# PLO2_v1.net
KiCad netlist of a schematic drawn in EAGLE
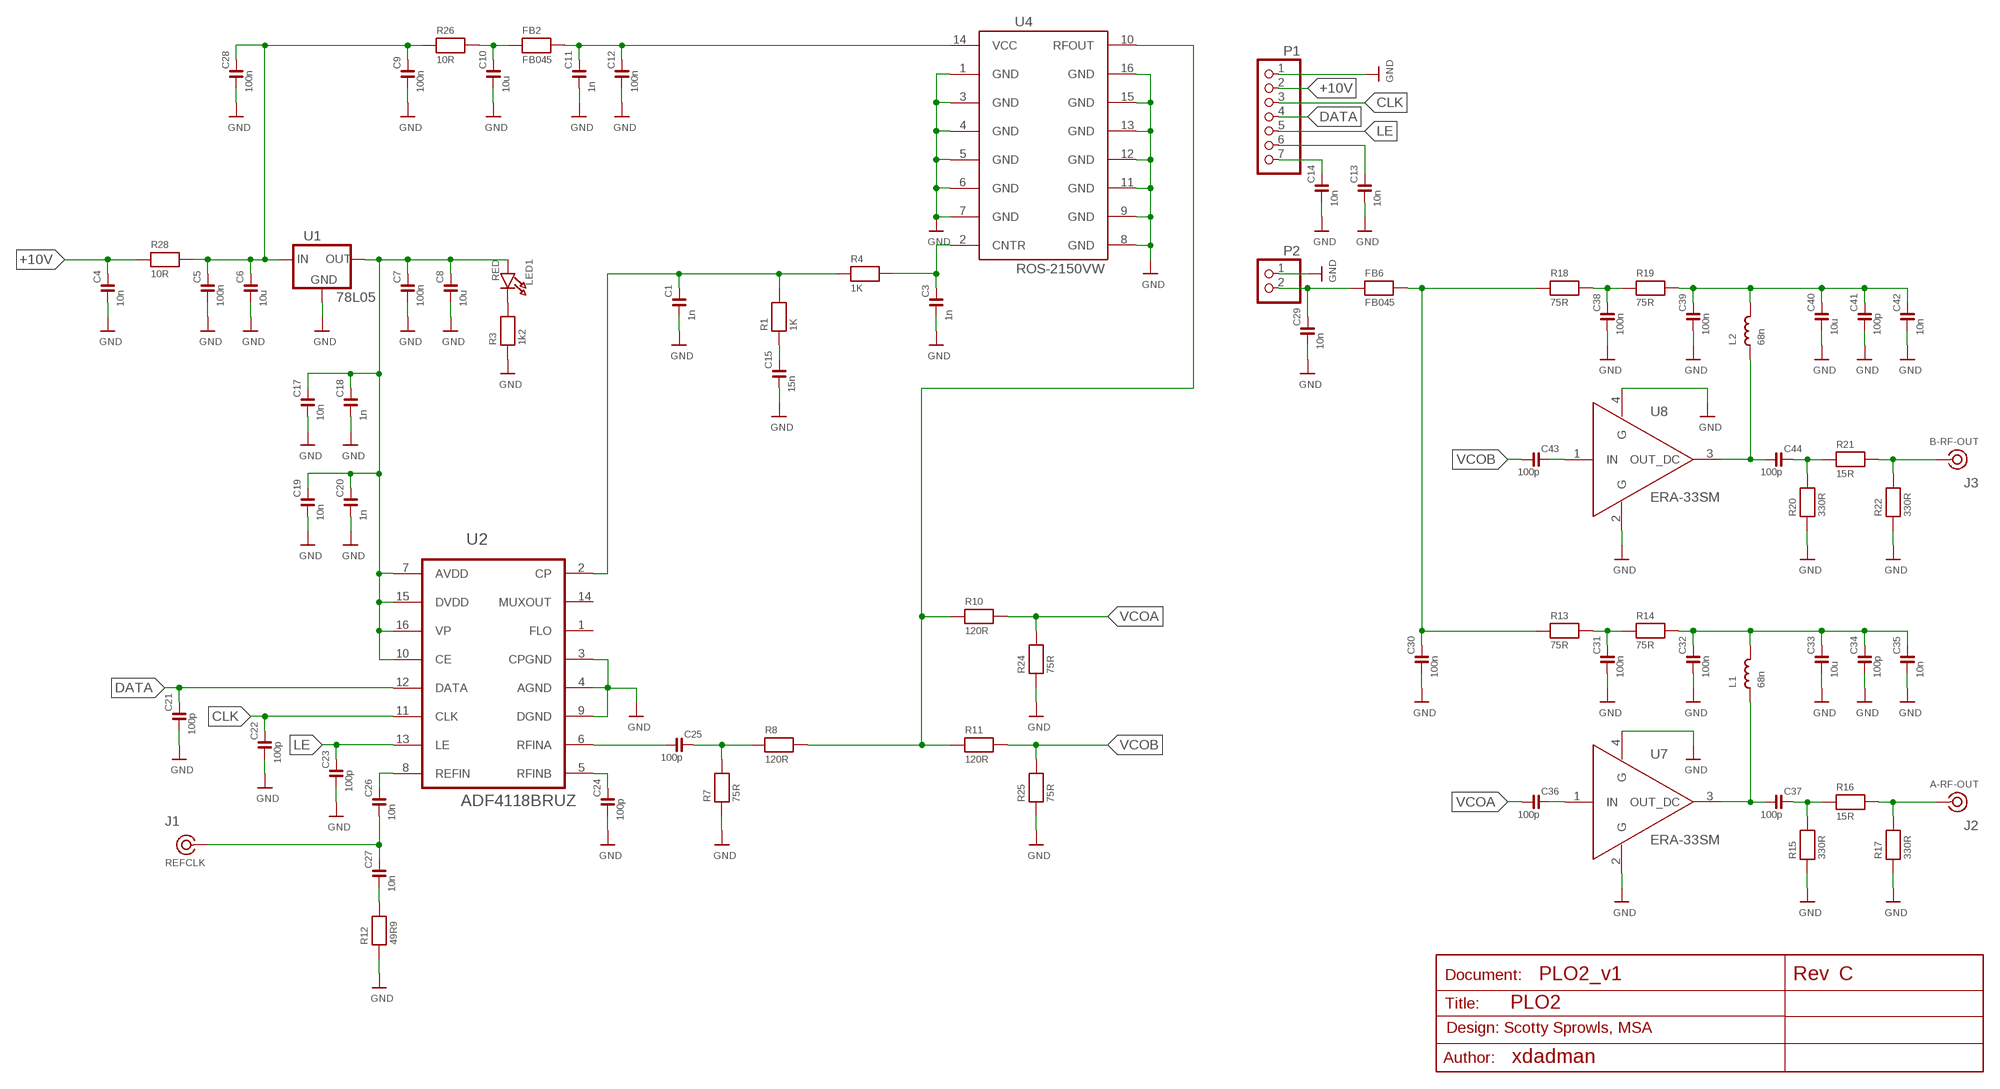
[diagram p0: schematic, sheet 1]

(export (version "E")
  (design (tool "Eeschema 10.0.6"))
  (components
    (comp (ref "C1")
      (value "1n")
      (footprint "eagle-import:C0805")
      (libsource (lib "eagle-import") (part "C08051N"))
    )
    (comp (ref "C3")
      (value "1n")
      (footprint "eagle-import:C0805")
      (libsource (lib "eagle-import") (part "C08051N"))
    )
    (comp (ref "C4")
      (value "10n")
      (footprint "eagle-import:C0805")
      (libsource (lib "eagle-import") (part "C080510N"))
    )
    (comp (ref "C5")
      (value "100n")
      (footprint "eagle-import:C0805")
      (libsource (lib "eagle-import") (part "C0805100N"))
    )
    (comp (ref "C6")
      (value "10u")
      (footprint "eagle-import:C1206")
      (libsource (lib "eagle-import") (part "CC120610U"))
    )
    (comp (ref "C7")
      (value "100n")
      (footprint "eagle-import:C0805")
      (libsource (lib "eagle-import") (part "C0805100N"))
    )
    (comp (ref "C8")
      (value "10u")
      (footprint "eagle-import:C1206")
      (libsource (lib "eagle-import") (part "CC120610U"))
    )
    (comp (ref "C9")
      (value "100n")
      (footprint "eagle-import:C0805")
      (libsource (lib "eagle-import") (part "C0805100N"))
    )
    (comp (ref "C10")
      (value "10u")
      (footprint "eagle-import:C1206")
      (libsource (lib "eagle-import") (part "CC120610U"))
    )
    (comp (ref "C11")
      (value "1n")
      (footprint "eagle-import:C0805")
      (libsource (lib "eagle-import") (part "C08051N"))
    )
    (comp (ref "C12")
      (value "100n")
      (footprint "eagle-import:C0805")
      (libsource (lib "eagle-import") (part "C0805100N"))
    )
    (comp (ref "C13")
      (value "10n")
      (footprint "eagle-import:C0805")
      (libsource (lib "eagle-import") (part "C080510N"))
    )
    (comp (ref "C14")
      (value "10n")
      (footprint "eagle-import:C0805")
      (libsource (lib "eagle-import") (part "C080510N"))
    )
    (comp (ref "C15")
      (value "15n")
      (footprint "eagle-import:C0805")
      (libsource (lib "eagle-import") (part "C080515N"))
    )
    (comp (ref "C17")
      (value "10n")
      (footprint "eagle-import:C0805")
      (libsource (lib "eagle-import") (part "C080510N"))
    )
    (comp (ref "C18")
      (value "1n")
      (footprint "eagle-import:C0805")
      (libsource (lib "eagle-import") (part "C08051N"))
    )
    (comp (ref "C19")
      (value "10n")
      (footprint "eagle-import:C0805")
      (libsource (lib "eagle-import") (part "C080510N"))
    )
    (comp (ref "C20")
      (value "1n")
      (footprint "eagle-import:C0805")
      (libsource (lib "eagle-import") (part "C08051N"))
    )
    (comp (ref "C21")
      (value "100p")
      (footprint "eagle-import:C0805")
      (libsource (lib "eagle-import") (part "C0805100P"))
    )
    (comp (ref "C22")
      (value "100p")
      (footprint "eagle-import:C0805")
      (libsource (lib "eagle-import") (part "C0805100P"))
    )
    (comp (ref "C23")
      (value "100p")
      (footprint "eagle-import:C0805")
      (libsource (lib "eagle-import") (part "C0805100P"))
    )
    (comp (ref "C24")
      (value "100p")
      (footprint "eagle-import:C0805")
      (libsource (lib "eagle-import") (part "C0805100P"))
    )
    (comp (ref "C25")
      (value "100p")
      (footprint "eagle-import:C0805")
      (libsource (lib "eagle-import") (part "C0805100P"))
    )
    (comp (ref "C26")
      (value "10n")
      (footprint "eagle-import:C0805")
      (libsource (lib "eagle-import") (part "C080510N"))
    )
    (comp (ref "C27")
      (value "10n")
      (footprint "eagle-import:C0805")
      (libsource (lib "eagle-import") (part "C080510N"))
    )
    (comp (ref "C28")
      (value "100n")
      (footprint "eagle-import:C0805")
      (libsource (lib "eagle-import") (part "C0805100N"))
    )
    (comp (ref "C29")
      (value "10n")
      (footprint "eagle-import:C0805")
      (libsource (lib "eagle-import") (part "C080510N"))
    )
    (comp (ref "C30")
      (value "100n")
      (footprint "eagle-import:C0805")
      (libsource (lib "eagle-import") (part "C0805100N"))
    )
    (comp (ref "C31")
      (value "100n")
      (footprint "eagle-import:C0805")
      (libsource (lib "eagle-import") (part "C0805100N"))
    )
    (comp (ref "C32")
      (value "100n")
      (footprint "eagle-import:C0805")
      (libsource (lib "eagle-import") (part "C0805100N"))
    )
    (comp (ref "C33")
      (value "10u")
      (footprint "eagle-import:C1206")
      (libsource (lib "eagle-import") (part "CC120610U"))
    )
    (comp (ref "C34")
      (value "100p")
      (footprint "eagle-import:C0805")
      (libsource (lib "eagle-import") (part "C0805100P"))
    )
    (comp (ref "C35")
      (value "10n")
      (footprint "eagle-import:C0805")
      (libsource (lib "eagle-import") (part "C080510N"))
    )
    (comp (ref "C36")
      (value "100p")
      (footprint "eagle-import:C0805")
      (libsource (lib "eagle-import") (part "C0805100P"))
    )
    (comp (ref "C37")
      (value "100p")
      (footprint "eagle-import:C0805")
      (libsource (lib "eagle-import") (part "C0805100P"))
    )
    (comp (ref "C38")
      (value "100n")
      (footprint "eagle-import:C0805")
      (libsource (lib "eagle-import") (part "C0805100N"))
    )
    (comp (ref "C39")
      (value "100n")
      (footprint "eagle-import:C0805")
      (libsource (lib "eagle-import") (part "C0805100N"))
    )
    (comp (ref "C40")
      (value "10u")
      (footprint "eagle-import:C1206")
      (libsource (lib "eagle-import") (part "CC120610U"))
    )
    (comp (ref "C41")
      (value "100p")
      (footprint "eagle-import:C0805")
      (libsource (lib "eagle-import") (part "C0805100P"))
    )
    (comp (ref "C42")
      (value "10n")
      (footprint "eagle-import:C0805")
      (libsource (lib "eagle-import") (part "C080510N"))
    )
    (comp (ref "C43")
      (value "100p")
      (footprint "eagle-import:C0805")
      (libsource (lib "eagle-import") (part "C0805100P"))
    )
    (comp (ref "C44")
      (value "100p")
      (footprint "eagle-import:C0805")
      (libsource (lib "eagle-import") (part "C0805100P"))
    )
    (comp (ref "FB2")
      (value "FB045")
      (footprint "eagle-import:R0805_SPC")
      (libsource (lib "eagle-import") (part "R0805FB045SPC"))
    )
    (comp (ref "FB6")
      (value "FB045")
      (footprint "eagle-import:R0805")
      (libsource (lib "eagle-import") (part "R0805FB045"))
    )
    (comp (ref "J1")
      (value "REFCLK")
      (footprint "eagle-import:SLIM_COAX_PAD")
      (libsource (lib "eagle-import") (part "COAX"))
    )
    (comp (ref "J2")
      (value "A-RF-OUT")
      (footprint "eagle-import:SLIM_COAX_PAD")
      (libsource (lib "eagle-import") (part "COAX"))
    )
    (comp (ref "J3")
      (value "B-RF-OUT")
      (footprint "eagle-import:SLIM_COAX_PAD")
      (libsource (lib "eagle-import") (part "COAX"))
    )
    (comp (ref "L1")
      (value "68n")
      (footprint "eagle-import:0603-MINI")
      (libsource (lib "eagle-import") (part "L060368N"))
    )
    (comp (ref "L2")
      (value "68n")
      (footprint "eagle-import:0603-MINI")
      (libsource (lib "eagle-import") (part "L060368N"))
    )
    (comp (ref "LED1")
      (value "RED")
      (footprint "eagle-import:CHIPLED_0603")
      (libsource (lib "eagle-import") (part "LED_0603_RED0603"))
    )
    (comp (ref "P1")
      (value "PINHD-1X7")
      (footprint "eagle-import:1X07")
      (libsource (lib "eagle-import") (part "PINHD-1X7"))
    )
    (comp (ref "P2")
      (value "PINHD-1X2")
      (footprint "eagle-import:1X02")
      (libsource (lib "eagle-import") (part "PINHD-1X2"))
    )
    (comp (ref "R1")
      (value "1K")
      (footprint "eagle-import:R0805")
      (libsource (lib "eagle-import") (part "R08051K"))
    )
    (comp (ref "R3")
      (value "1k2")
      (footprint "eagle-import:R0805")
      (libsource (lib "eagle-import") (part "R08051K2"))
    )
    (comp (ref "R4")
      (value "1K")
      (footprint "eagle-import:R0805")
      (libsource (lib "eagle-import") (part "R08051K"))
    )
    (comp (ref "R7")
      (value "75R")
      (footprint "eagle-import:R0805")
      (libsource (lib "eagle-import") (part "R080575R"))
    )
    (comp (ref "R8")
      (value "120R")
      (footprint "eagle-import:R0805")
      (libsource (lib "eagle-import") (part "R0805120R"))
    )
    (comp (ref "R10")
      (value "120R")
      (footprint "eagle-import:R0805")
      (libsource (lib "eagle-import") (part "R0805120R"))
    )
    (comp (ref "R11")
      (value "120R")
      (footprint "eagle-import:R0805")
      (libsource (lib "eagle-import") (part "R0805120R"))
    )
    (comp (ref "R12")
      (value "49R9")
      (footprint "eagle-import:R0805")
      (libsource (lib "eagle-import") (part "R080549R9"))
    )
    (comp (ref "R13")
      (value "75R")
      (footprint "eagle-import:R0805")
      (libsource (lib "eagle-import") (part "R080575R"))
    )
    (comp (ref "R14")
      (value "75R")
      (footprint "eagle-import:R0805")
      (libsource (lib "eagle-import") (part "R080575R"))
    )
    (comp (ref "R15")
      (value "330R")
      (footprint "eagle-import:R0805")
      (libsource (lib "eagle-import") (part "R0805330R"))
    )
    (comp (ref "R16")
      (value "15R")
      (footprint "eagle-import:0805")
      (libsource (lib "eagle-import") (part "R080515R"))
    )
    (comp (ref "R17")
      (value "330R")
      (footprint "eagle-import:R0805")
      (libsource (lib "eagle-import") (part "R0805330R"))
    )
    (comp (ref "R18")
      (value "75R")
      (footprint "eagle-import:R0805")
      (libsource (lib "eagle-import") (part "R080575R"))
    )
    (comp (ref "R19")
      (value "75R")
      (footprint "eagle-import:R0805")
      (libsource (lib "eagle-import") (part "R080575R"))
    )
    (comp (ref "R20")
      (value "330R")
      (footprint "eagle-import:R0805")
      (libsource (lib "eagle-import") (part "R0805330R"))
    )
    (comp (ref "R21")
      (value "15R")
      (footprint "eagle-import:0805")
      (libsource (lib "eagle-import") (part "R080515R"))
    )
    (comp (ref "R22")
      (value "330R")
      (footprint "eagle-import:R0805")
      (libsource (lib "eagle-import") (part "R0805330R"))
    )
    (comp (ref "R24")
      (value "75R")
      (footprint "eagle-import:R0805")
      (libsource (lib "eagle-import") (part "R080575R"))
    )
    (comp (ref "R25")
      (value "75R")
      (footprint "eagle-import:R0805")
      (libsource (lib "eagle-import") (part "R080575R"))
    )
    (comp (ref "R26")
      (value "10R")
      (footprint "eagle-import:R0805")
      (libsource (lib "eagle-import") (part "R080510R"))
    )
    (comp (ref "R28")
      (value "10R")
      (footprint "eagle-import:R0805")
      (libsource (lib "eagle-import") (part "R080510R"))
    )
    (comp (ref "U1")
      (value "78L05")
      (footprint "eagle-import:SOT89")
      (libsource (lib "eagle-import") (part "78MXXL78L05"))
    )
    (comp (ref "U2")
      (value "ADF4118BRUZ")
      (footprint "eagle-import:SOIC65P640X120-16N")
      (libsource (lib "eagle-import") (part "ADF4118BRUZ"))
    )
    (comp (ref "U4")
      (value "ROS-2150VW")
      (footprint "eagle-import:ROS-2150VW")
      (libsource (lib "eagle-import") (part "ROS-2150VW"))
    )
    (comp (ref "U7")
      (value "ERA-33SM")
      (footprint "eagle-import:WW107")
      (libsource (lib "eagle-import") (part "ERA-33SM"))
    )
    (comp (ref "U8")
      (value "ERA-33SM")
      (footprint "eagle-import:WW107")
      (libsource (lib "eagle-import") (part "ERA-33SM"))
    )
  )
  (nets
    (net (code "1") (name "+10V") (class "Default")
      (node (ref "C4") (pin "2") (pinfunction "2_2") (pintype "passive"))
      (node (ref "P1") (pin "2") (pinfunction "2_2") (pintype "passive"))
      (node (ref "R28") (pin "1") (pinfunction "1_1") (pintype "passive"))
    )
    (net (code "2") (name "CLK") (class "Default")
      (node (ref "C22") (pin "2") (pinfunction "2_2") (pintype "passive"))
      (node (ref "P1") (pin "3") (pinfunction "3_3") (pintype "passive"))
      (node (ref "U2") (pin "11") (pinfunction "CLK_11") (pintype "input"))
    )
    (net (code "3") (name "DATA") (class "Default")
      (node (ref "C21") (pin "2") (pinfunction "2_2") (pintype "passive"))
      (node (ref "P1") (pin "4") (pinfunction "4_4") (pintype "passive"))
      (node (ref "U2") (pin "12") (pinfunction "DATA_12") (pintype "input"))
    )
    (net (code "4") (name "GND") (class "Default")
      (node (ref "C1") (pin "1") (pinfunction "1_1") (pintype "passive"))
      (node (ref "C10") (pin "1") (pinfunction "1_1") (pintype "passive"))
      (node (ref "C11") (pin "1") (pinfunction "1_1") (pintype "passive"))
      (node (ref "C12") (pin "1") (pinfunction "1_1") (pintype "passive"))
      (node (ref "C13") (pin "1") (pinfunction "1_1") (pintype "passive"))
      (node (ref "C14") (pin "1") (pinfunction "1_1") (pintype "passive"))
      (node (ref "C15") (pin "1") (pinfunction "1_1") (pintype "passive"))
      (node (ref "C17") (pin "1") (pinfunction "1_1") (pintype "passive"))
      (node (ref "C18") (pin "1") (pinfunction "1_1") (pintype "passive"))
      (node (ref "C19") (pin "1") (pinfunction "1_1") (pintype "passive"))
      (node (ref "C20") (pin "1") (pinfunction "1_1") (pintype "passive"))
      (node (ref "C21") (pin "1") (pinfunction "1_1") (pintype "passive"))
      (node (ref "C22") (pin "1") (pinfunction "1_1") (pintype "passive"))
      (node (ref "C23") (pin "1") (pinfunction "1_1") (pintype "passive"))
      (node (ref "C24") (pin "1") (pinfunction "1_1") (pintype "passive"))
      (node (ref "C28") (pin "1") (pinfunction "1_1") (pintype "passive"))
      (node (ref "C29") (pin "1") (pinfunction "1_1") (pintype "passive"))
      (node (ref "C3") (pin "1") (pinfunction "1_1") (pintype "passive"))
      (node (ref "C30") (pin "1") (pinfunction "1_1") (pintype "passive"))
      (node (ref "C31") (pin "1") (pinfunction "1_1") (pintype "passive"))
      (node (ref "C32") (pin "1") (pinfunction "1_1") (pintype "passive"))
      (node (ref "C33") (pin "1") (pinfunction "1_1") (pintype "passive"))
      (node (ref "C34") (pin "1") (pinfunction "1_1") (pintype "passive"))
      (node (ref "C35") (pin "1") (pinfunction "1_1") (pintype "passive"))
      (node (ref "C38") (pin "1") (pinfunction "1_1") (pintype "passive"))
      (node (ref "C39") (pin "1") (pinfunction "1_1") (pintype "passive"))
      (node (ref "C4") (pin "1") (pinfunction "1_1") (pintype "passive"))
      (node (ref "C40") (pin "1") (pinfunction "1_1") (pintype "passive"))
      (node (ref "C41") (pin "1") (pinfunction "1_1") (pintype "passive"))
      (node (ref "C42") (pin "1") (pinfunction "1_1") (pintype "passive"))
      (node (ref "C5") (pin "1") (pinfunction "1_1") (pintype "passive"))
      (node (ref "C6") (pin "1") (pinfunction "1_1") (pintype "passive"))
      (node (ref "C7") (pin "1") (pinfunction "1_1") (pintype "passive"))
      (node (ref "C8") (pin "1") (pinfunction "1_1") (pintype "passive"))
      (node (ref "C9") (pin "1") (pinfunction "1_1") (pintype "passive"))
      (node (ref "P1") (pin "1") (pinfunction "1_1") (pintype "passive"))
      (node (ref "P2") (pin "1") (pinfunction "1_1") (pintype "passive"))
      (node (ref "R12") (pin "1") (pinfunction "1_1") (pintype "passive"))
      (node (ref "R15") (pin "1") (pinfunction "1_1") (pintype "passive"))
      (node (ref "R17") (pin "1") (pinfunction "1_1") (pintype "passive"))
      (node (ref "R20") (pin "1") (pinfunction "1_1") (pintype "passive"))
      (node (ref "R22") (pin "1") (pinfunction "1_1") (pintype "passive"))
      (node (ref "R24") (pin "1") (pinfunction "1_1") (pintype "passive"))
      (node (ref "R25") (pin "1") (pinfunction "1_1") (pintype "passive"))
      (node (ref "R3") (pin "1") (pinfunction "1_1") (pintype "passive"))
      (node (ref "R7") (pin "1") (pinfunction "1_1") (pintype "passive"))
      (node (ref "U1") (pin "2") (pinfunction "GND_2") (pintype "input"))
      (node (ref "U1") (pin "4") (pinfunction "GND_4") (pintype "input"))
      (node (ref "U2") (pin "3") (pinfunction "CPGND_3") (pintype "passive"))
      (node (ref "U2") (pin "4") (pinfunction "AGND_4") (pintype "passive"))
      (node (ref "U2") (pin "9") (pinfunction "DGND_9") (pintype "passive"))
      (node (ref "U4") (pin "1") (pinfunction "GND_1") (pintype "bidirectional"))
      (node (ref "U4") (pin "11") (pinfunction "GND_11") (pintype "bidirectional"))
      (node (ref "U4") (pin "12") (pinfunction "GND_12") (pintype "bidirectional"))
      (node (ref "U4") (pin "13") (pinfunction "GND_13") (pintype "bidirectional"))
      (node (ref "U4") (pin "15") (pinfunction "GND_15") (pintype "bidirectional"))
      (node (ref "U4") (pin "16") (pinfunction "GND_16") (pintype "bidirectional"))
      (node (ref "U4") (pin "3") (pinfunction "GND_3") (pintype "bidirectional"))
      (node (ref "U4") (pin "4") (pinfunction "GND_4") (pintype "bidirectional"))
      (node (ref "U4") (pin "5") (pinfunction "GND_5") (pintype "bidirectional"))
      (node (ref "U4") (pin "6") (pinfunction "GND_6") (pintype "bidirectional"))
      (node (ref "U4") (pin "7") (pinfunction "GND_7") (pintype "bidirectional"))
      (node (ref "U4") (pin "8") (pinfunction "GND_8") (pintype "bidirectional"))
      (node (ref "U4") (pin "9") (pinfunction "GND_9") (pintype "bidirectional"))
      (node (ref "U7") (pin "2") (pinfunction "G_2") (pintype "bidirectional"))
      (node (ref "U7") (pin "4") (pinfunction "G_4") (pintype "bidirectional"))
      (node (ref "U8") (pin "2") (pinfunction "G_2") (pintype "bidirectional"))
      (node (ref "U8") (pin "4") (pinfunction "G_4") (pintype "bidirectional"))
    )
    (net (code "5") (name "LE") (class "Default")
      (node (ref "C23") (pin "2") (pinfunction "2_2") (pintype "passive"))
      (node (ref "P1") (pin "5") (pinfunction "5_5") (pintype "passive"))
      (node (ref "U2") (pin "13") (pinfunction "LE_13") (pintype "input"))
    )
    (net (code "6") (name "Net-(C10-Pad2)") (class "Default")
      (node (ref "C10") (pin "2") (pinfunction "2_2") (pintype "passive"))
      (node (ref "FB2") (pin "1") (pinfunction "1_1") (pintype "passive"))
      (node (ref "R26") (pin "2") (pinfunction "2_2") (pintype "passive"))
    )
    (net (code "7") (name "Net-(C13-Pad2)") (class "Default")
      (node (ref "C13") (pin "2") (pinfunction "2_2") (pintype "passive"))
      (node (ref "P1") (pin "6") (pinfunction "6_6") (pintype "passive"))
    )
    (net (code "8") (name "Net-(C14-Pad2)") (class "Default")
      (node (ref "C14") (pin "2") (pinfunction "2_2") (pintype "passive"))
      (node (ref "P1") (pin "7") (pinfunction "7_7") (pintype "passive"))
    )
    (net (code "9") (name "Net-(C15-Pad2)") (class "Default")
      (node (ref "C15") (pin "2") (pinfunction "2_2") (pintype "passive"))
      (node (ref "R1") (pin "1") (pinfunction "1_1") (pintype "passive"))
    )
    (net (code "10") (name "Net-(C25-Pad2)") (class "Default")
      (node (ref "C25") (pin "2") (pinfunction "2_2") (pintype "passive"))
      (node (ref "R7") (pin "2") (pinfunction "2_2") (pintype "passive"))
      (node (ref "R8") (pin "1") (pinfunction "1_1") (pintype "passive"))
    )
    (net (code "11") (name "Net-(C27-Pad1)") (class "Default")
      (node (ref "C27") (pin "1") (pinfunction "1_1") (pintype "passive"))
      (node (ref "R12") (pin "2") (pinfunction "2_2") (pintype "passive"))
    )
    (net (code "12") (name "Net-(C29-Pad2)") (class "Default")
      (node (ref "C29") (pin "2") (pinfunction "2_2") (pintype "passive"))
      (node (ref "FB6") (pin "1") (pinfunction "1_1") (pintype "passive"))
      (node (ref "P2") (pin "2") (pinfunction "2_2") (pintype "passive"))
    )
    (net (code "13") (name "Net-(C30-Pad2)") (class "Default")
      (node (ref "C30") (pin "2") (pinfunction "2_2") (pintype "passive"))
      (node (ref "FB6") (pin "2") (pinfunction "2_2") (pintype "passive"))
      (node (ref "R13") (pin "1") (pinfunction "1_1") (pintype "passive"))
      (node (ref "R18") (pin "1") (pinfunction "1_1") (pintype "passive"))
    )
    (net (code "14") (name "Net-(C31-Pad2)") (class "Default")
      (node (ref "C31") (pin "2") (pinfunction "2_2") (pintype "passive"))
      (node (ref "R13") (pin "2") (pinfunction "2_2") (pintype "passive"))
      (node (ref "R14") (pin "1") (pinfunction "1_1") (pintype "passive"))
    )
    (net (code "15") (name "Net-(C32-Pad2)") (class "Default")
      (node (ref "C32") (pin "2") (pinfunction "2_2") (pintype "passive"))
      (node (ref "C33") (pin "2") (pinfunction "2_2") (pintype "passive"))
      (node (ref "C34") (pin "2") (pinfunction "2_2") (pintype "passive"))
      (node (ref "C35") (pin "2") (pinfunction "2_2") (pintype "passive"))
      (node (ref "L1") (pin "2") (pinfunction "2_2") (pintype "passive"))
      (node (ref "R14") (pin "2") (pinfunction "2_2") (pintype "passive"))
    )
    (net (code "16") (name "Net-(C37-Pad2)") (class "Default")
      (node (ref "C37") (pin "2") (pinfunction "2_2") (pintype "passive"))
      (node (ref "R15") (pin "2") (pinfunction "2_2") (pintype "passive"))
      (node (ref "R16") (pin "1") (pinfunction "1_1") (pintype "passive"))
    )
    (net (code "17") (name "Net-(C38-Pad2)") (class "Default")
      (node (ref "C38") (pin "2") (pinfunction "2_2") (pintype "passive"))
      (node (ref "R18") (pin "2") (pinfunction "2_2") (pintype "passive"))
      (node (ref "R19") (pin "1") (pinfunction "1_1") (pintype "passive"))
    )
    (net (code "18") (name "Net-(C39-Pad2)") (class "Default")
      (node (ref "C39") (pin "2") (pinfunction "2_2") (pintype "passive"))
      (node (ref "C40") (pin "2") (pinfunction "2_2") (pintype "passive"))
      (node (ref "C41") (pin "2") (pinfunction "2_2") (pintype "passive"))
      (node (ref "C42") (pin "2") (pinfunction "2_2") (pintype "passive"))
      (node (ref "L2") (pin "2") (pinfunction "2_2") (pintype "passive"))
      (node (ref "R19") (pin "2") (pinfunction "2_2") (pintype "passive"))
    )
    (net (code "19") (name "Net-(C44-Pad2)") (class "Default")
      (node (ref "C44") (pin "2") (pinfunction "2_2") (pintype "passive"))
      (node (ref "R20") (pin "2") (pinfunction "2_2") (pintype "passive"))
      (node (ref "R21") (pin "1") (pinfunction "1_1") (pintype "passive"))
    )
    (net (code "20") (name "Net-(J1A-1)") (class "Default")
      (node (ref "C26") (pin "1") (pinfunction "1_1") (pintype "passive"))
      (node (ref "C27") (pin "2") (pinfunction "2_2") (pintype "passive"))
      (node (ref "J1") (pin "SIG") (pinfunction "1_SIG") (pintype "passive"))
    )
    (net (code "21") (name "Net-(J2A-1)") (class "Default")
      (node (ref "J2") (pin "SIG") (pinfunction "1_SIG") (pintype "passive"))
      (node (ref "R16") (pin "2") (pinfunction "2_2") (pintype "passive"))
      (node (ref "R17") (pin "2") (pinfunction "2_2") (pintype "passive"))
    )
    (net (code "22") (name "Net-(J3A-1)") (class "Default")
      (node (ref "J3") (pin "SIG") (pinfunction "1_SIG") (pintype "passive"))
      (node (ref "R21") (pin "2") (pinfunction "2_2") (pintype "passive"))
      (node (ref "R22") (pin "2") (pinfunction "2_2") (pintype "passive"))
    )
    (net (code "23") (name "Net-(LED1-PadC)") (class "Default")
      (node (ref "LED1") (pin "C") (pinfunction "C_C") (pintype "passive"))
      (node (ref "R3") (pin "2") (pinfunction "2_2") (pintype "passive"))
    )
    (net (code "24") (name "Net-(U1-IN)") (class "Default")
      (node (ref "C28") (pin "2") (pinfunction "2_2") (pintype "passive"))
      (node (ref "C5") (pin "2") (pinfunction "2_2") (pintype "passive"))
      (node (ref "C6") (pin "2") (pinfunction "2_2") (pintype "passive"))
      (node (ref "C9") (pin "2") (pinfunction "2_2") (pintype "passive"))
      (node (ref "R26") (pin "1") (pinfunction "1_1") (pintype "passive"))
      (node (ref "R28") (pin "2") (pinfunction "2_2") (pintype "passive"))
      (node (ref "U1") (pin "3") (pinfunction "IN_3") (pintype "input"))
    )
    (net (code "25") (name "Net-(U1-OUT)") (class "Default")
      (node (ref "C17") (pin "2") (pinfunction "2_2") (pintype "passive"))
      (node (ref "C18") (pin "2") (pinfunction "2_2") (pintype "passive"))
      (node (ref "C19") (pin "2") (pinfunction "2_2") (pintype "passive"))
      (node (ref "C20") (pin "2") (pinfunction "2_2") (pintype "passive"))
      (node (ref "C7") (pin "2") (pinfunction "2_2") (pintype "passive"))
      (node (ref "C8") (pin "2") (pinfunction "2_2") (pintype "passive"))
      (node (ref "LED1") (pin "A") (pinfunction "A_A") (pintype "passive"))
      (node (ref "U1") (pin "1") (pinfunction "OUT_1") (pintype "passive"))
      (node (ref "U2") (pin "10") (pinfunction "CE_10") (pintype "input"))
      (node (ref "U2") (pin "15") (pinfunction "DVDD_15") (pintype "power_in"))
      (node (ref "U2") (pin "16") (pinfunction "VP_16") (pintype "power_in"))
      (node (ref "U2") (pin "7") (pinfunction "AVDD_7") (pintype "power_in"))
    )
    (net (code "26") (name "Net-(U2-CP)") (class "Default")
      (node (ref "C1") (pin "2") (pinfunction "2_2") (pintype "passive"))
      (node (ref "R1") (pin "2") (pinfunction "2_2") (pintype "passive"))
      (node (ref "R4") (pin "1") (pinfunction "1_1") (pintype "passive"))
      (node (ref "U2") (pin "2") (pinfunction "CP_2") (pintype "output"))
    )
    (net (code "27") (name "Net-(U2-REFIN)") (class "Default")
      (node (ref "C26") (pin "2") (pinfunction "2_2") (pintype "passive"))
      (node (ref "U2") (pin "8") (pinfunction "REFIN_8") (pintype "input"))
    )
    (net (code "28") (name "Net-(U2-RFINA)") (class "Default")
      (node (ref "C25") (pin "1") (pinfunction "1_1") (pintype "passive"))
      (node (ref "U2") (pin "6") (pinfunction "RFINA_6") (pintype "input"))
    )
    (net (code "29") (name "Net-(U2-RFINB)") (class "Default")
      (node (ref "C24") (pin "2") (pinfunction "2_2") (pintype "passive"))
      (node (ref "U2") (pin "5") (pinfunction "RFINB_5") (pintype "input"))
    )
    (net (code "30") (name "Net-(U4-CNTR)") (class "Default")
      (node (ref "C3") (pin "2") (pinfunction "2_2") (pintype "passive"))
      (node (ref "R4") (pin "2") (pinfunction "2_2") (pintype "passive"))
      (node (ref "U4") (pin "2") (pinfunction "CNTR_2") (pintype "bidirectional"))
    )
    (net (code "31") (name "Net-(U4-RFOUT)") (class "Default")
      (node (ref "R10") (pin "1") (pinfunction "1_1") (pintype "passive"))
      (node (ref "R11") (pin "1") (pinfunction "1_1") (pintype "passive"))
      (node (ref "R8") (pin "2") (pinfunction "2_2") (pintype "passive"))
      (node (ref "U4") (pin "10") (pinfunction "RFOUT_10") (pintype "bidirectional"))
    )
    (net (code "32") (name "Net-(U4-VCC)") (class "Default")
      (node (ref "C11") (pin "2") (pinfunction "2_2") (pintype "passive"))
      (node (ref "C12") (pin "2") (pinfunction "2_2") (pintype "passive"))
      (node (ref "FB2") (pin "2") (pinfunction "2_2") (pintype "passive"))
      (node (ref "U4") (pin "14") (pinfunction "VCC_14") (pintype "bidirectional"))
    )
    (net (code "33") (name "Net-(U7-IN)") (class "Default")
      (node (ref "C36") (pin "2") (pinfunction "2_2") (pintype "passive"))
      (node (ref "U7") (pin "1") (pinfunction "IN_1") (pintype "bidirectional"))
    )
    (net (code "34") (name "Net-(U7-OUT_DC)") (class "Default")
      (node (ref "C37") (pin "1") (pinfunction "1_1") (pintype "passive"))
      (node (ref "L1") (pin "1") (pinfunction "1_1") (pintype "passive"))
      (node (ref "U7") (pin "3") (pinfunction "OUT_DC_3") (pintype "bidirectional"))
    )
    (net (code "35") (name "Net-(U8-IN)") (class "Default")
      (node (ref "C43") (pin "2") (pinfunction "2_2") (pintype "passive"))
      (node (ref "U8") (pin "1") (pinfunction "IN_1") (pintype "bidirectional"))
    )
    (net (code "36") (name "Net-(U8-OUT_DC)") (class "Default")
      (node (ref "C44") (pin "1") (pinfunction "1_1") (pintype "passive"))
      (node (ref "L2") (pin "1") (pinfunction "1_1") (pintype "passive"))
      (node (ref "U8") (pin "3") (pinfunction "OUT_DC_3") (pintype "bidirectional"))
    )
    (net (code "37") (name "VCOA") (class "Default")
      (node (ref "C36") (pin "1") (pinfunction "1_1") (pintype "passive"))
      (node (ref "R10") (pin "2") (pinfunction "2_2") (pintype "passive"))
      (node (ref "R24") (pin "2") (pinfunction "2_2") (pintype "passive"))
    )
    (net (code "38") (name "VCOB") (class "Default")
      (node (ref "C43") (pin "1") (pinfunction "1_1") (pintype "passive"))
      (node (ref "R11") (pin "2") (pinfunction "2_2") (pintype "passive"))
      (node (ref "R25") (pin "2") (pinfunction "2_2") (pintype "passive"))
    )
    (net (code "39") (name "unconnected-(U2-FLO-Pad1)") (class "Default")
      (node (ref "U2") (pin "1") (pinfunction "FLO_1") (pintype "output"))
    )
    (net (code "40") (name "unconnected-(U2-MUXOUT-Pad14)") (class "Default")
      (node (ref "U2") (pin "14") (pinfunction "MUXOUT_14") (pintype "output"))
    )
  )
)
